# FPGA_Configuration.net
KiCad netlist of a schematic drawn in Altium Designer
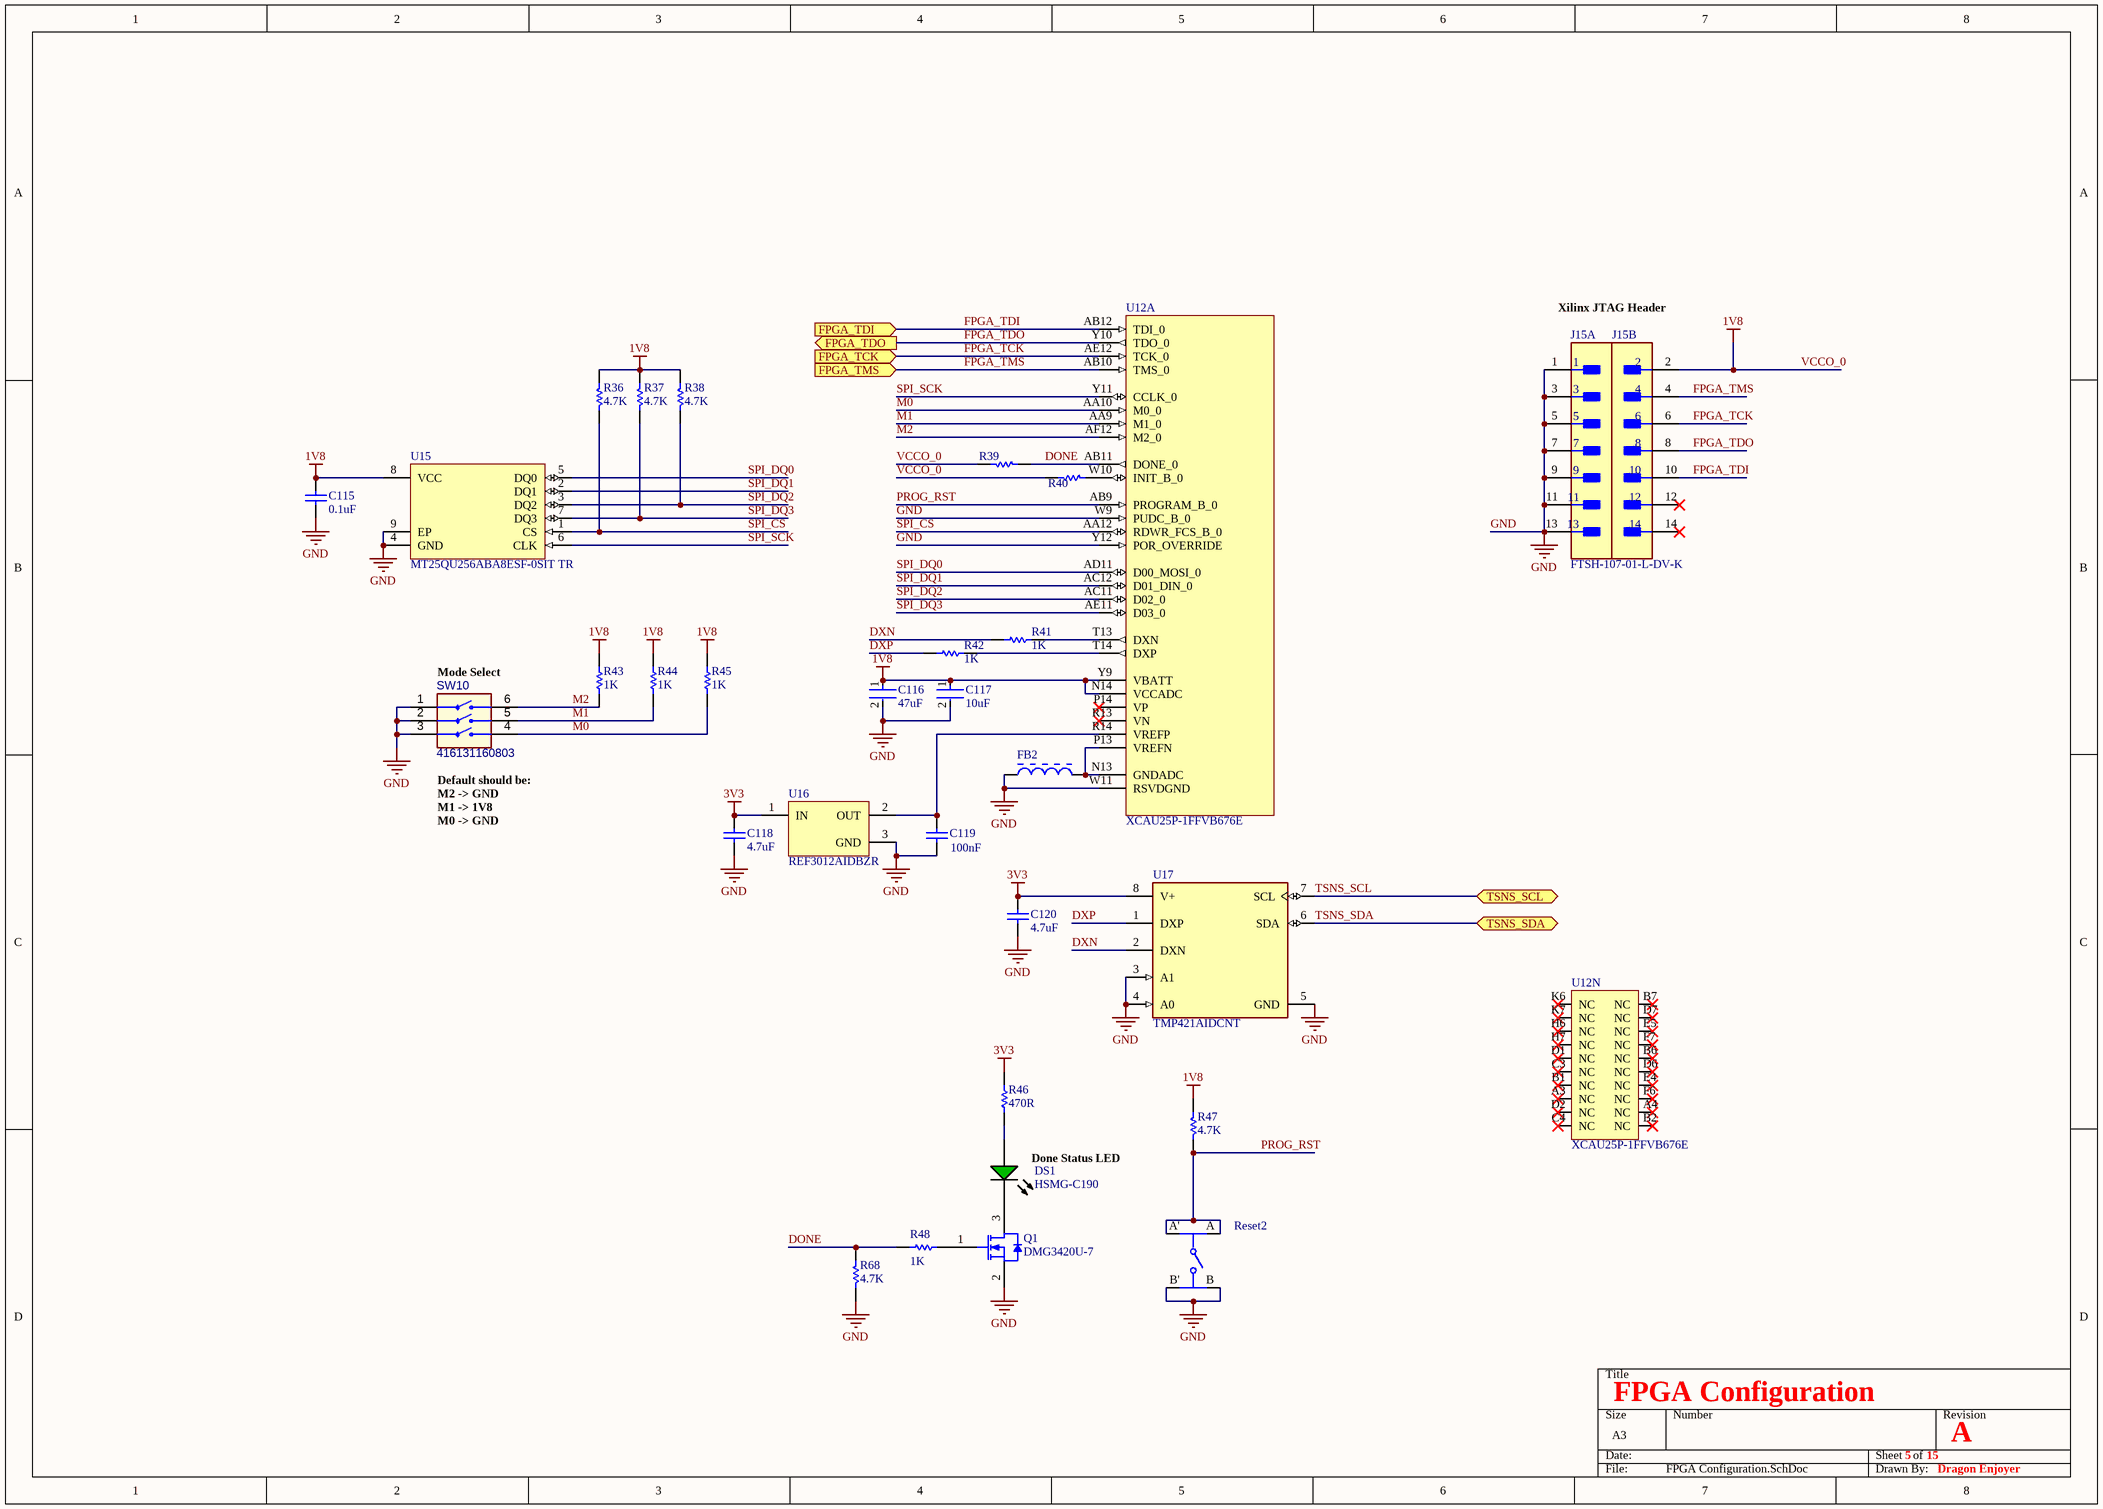
[diagram p0: FPGA Configuration.SchDoc]

(export (version "E")
  (design (tool "Eeschema 10.0.6"))
  (components
    (comp (ref "C115")
      (value "0.1uF")
      (footprint "CAPC1005X56X25LL10T15")
      (fields
        (field (name "MANUFACTURER") "AVX Interconnect / Elco")
        (field (name "PART NUMBER") "04026D104KAT2A")
      )
      (libsource (lib "Altium Content Vault") (part "CAP"))
    )
    (comp (ref "C116")
      (value "GRM188C80E476ME05D")
      (footprint "FP-GRM188-0_2-IPC_C")
      (description "Chip Multilayer Ceramic Capacitors for General Purpose, 0603, 47uF, X6S, 22%, 20%, 2.5V")
      (fields (field (name "TOLERANCE") "20%") (field (name "CAPACITANCE") "47uF"))
      (libsource (lib "Altium Content Vault") (part "11868f565c42a9108669ba33697ecf6"))
    )
    (comp (ref "C117")
      (value "GRM155C80J106ME11D")
      (footprint "FP-GRM15-0_2-MFG")
      (description "CAP CER 10UF 6.3V X6S 0402")
      (fields
        (field (name "TOLERANCE") "20%")
        (field (name "OCTOPART") "https://octopart.com/grm155c80j106me11d-murata-71220993")
        (field (name "CAPACITANCE") "10uF")
      )
      (libsource (lib "Altium Content Vault") (part "b4654b650e69147ec39a6b967a45e02"))
    )
    (comp (ref "C118")
      (value "4.7uF")
      (footprint "CAPC2013X135X45NL10T25")
      (fields (field (name "PART NUMBER") "GRM21BR61E475KA12L") (field (name "MANUFACTURER") "Murata"))
      (libsource (lib "Altium Content Vault") (part "CAP"))
    )
    (comp (ref "C119")
      (value "GRM188R71H104KA93D")
      (footprint "CAPC1608X90X35ML10T15")
      (description "Chip Capacitor, 0.1 uF, +/- 10%, 50 V, -55 to 125 degC, 0603 (1608 Metric), RoHS, Tape and Reel")
      (fields
        (field (name "TOLERANCE") "10%")
        (field (name "CAPACITANCE") "100nF")
        (field (name "VOLTAGE") "50V")
      )
      (libsource (lib "Altium Content Vault") (part "CAP-NP-2"))
    )
    (comp (ref "C120")
      (value "4.7uF")
      (footprint "CAPC2013X135X45NL10T25")
      (fields (field (name "PART NUMBER") "GRM21BR61E475KA12L") (field (name "MANUFACTURER") "Murata"))
      (libsource (lib "Altium Content Vault") (part "CAP"))
    )
    (comp (ref "DS1")
      (value "HSMG-C190")
      (footprint "AVAG-HSMX-C190_V")
      (description "Chip LED, Green, 2.2 V, -40 to 85 degC, 2-Pin SMD, RoHS, Tape and Reel")
      (libsource (lib "Altium Content Vault") (part "LED-GREEN-AK-2"))
    )
    (comp (ref "FB2")
      (value "BLM15AG100SN1D")
      (footprint "MURA-BLM15-CHIP-2_V")
      (fields (field (name "MANUFACTURER") "Murata"))
      (libsource (lib "Altium Content Vault") (part "MURA-FB-2"))
    )
    (comp (ref "J15")
      (value "FTSH-107-01-L-DV-K")
      (footprint "FP-FTSH-107-01-L-DV-K-MFG")
      (description "CONN HEADER SMD 14POS 1.27MM")
      (libsource (lib "") (part "7644e1a88aa4da17242a9b8d8257442_1"))
    )
    (comp (ref "Q1")
      (value "DMG3420U-7")
      (footprint "DIOD-SOT23-3_B_V")
      (description "N-Channel Enhancement Mode MOSFET, 20 V, -55 to 150 degC, 3-Pin SOT23, RoHS, Tape and Reel")
      (fields (field (name "MANUFACTURER") "Diodes Inc"))
      (libsource (lib "Altium Content Vault") (part "NEMOS-GSD-3"))
    )
    (comp (ref "R36")
      (value "4.7K")
      (footprint "RESC1005X40X25LL05T10")
      (fields (field (name "PART NUMBER") "RC0402JR-074K7L") (field (name "MANUFACTURER") "Yageo / Phycomp"))
      (libsource (lib "Altium Content Vault") (part "RES"))
    )
    (comp (ref "R37")
      (value "4.7K")
      (footprint "RESC1005X40X25LL05T10")
      (fields (field (name "PART NUMBER") "RC0402JR-074K7L") (field (name "MANUFACTURER") "Yageo / Phycomp"))
      (libsource (lib "Altium Content Vault") (part "RES"))
    )
    (comp (ref "R38")
      (value "4.7K")
      (footprint "RESC1005X40X25LL05T10")
      (fields (field (name "PART NUMBER") "RC0402JR-074K7L") (field (name "MANUFACTURER") "Yageo / Phycomp"))
      (libsource (lib "Altium Content Vault") (part "RES"))
    )
    (comp (ref "R39")
      (value "RC0402JR-074K7L")
      (footprint "RESC1005X40X25LL05T10")
      (fields (field (name "MANUFACTURER") "Yageo / Phycomp"))
      (libsource (lib "Altium Content Vault") (part "RES"))
    )
    (comp (ref "R40")
      (value "RC0402JR-074K7L")
      (footprint "RESC1005X40X25LL05T10")
      (fields (field (name "MANUFACTURER") "Yageo / Phycomp"))
      (libsource (lib "Altium Content Vault") (part "RES"))
    )
    (comp (ref "R41")
      (value "1K")
      (footprint "RESC1005X40X25NL05T10")
      (fields (field (name "PART NUMBER") "RC0402FR-071KL") (field (name "MANUFACTURER") "Yageo / Phycomp"))
      (libsource (lib "Altium Content Vault") (part "RES"))
    )
    (comp (ref "R42")
      (value "1K")
      (footprint "RESC1005X40X25NL05T10")
      (fields (field (name "PART NUMBER") "RC0402FR-071KL") (field (name "MANUFACTURER") "Yageo / Phycomp"))
      (libsource (lib "Altium Content Vault") (part "RES"))
    )
    (comp (ref "R43")
      (value "1K")
      (footprint "RESC1005X40X25NL05T10")
      (fields (field (name "PART NUMBER") "RC0402FR-071KL") (field (name "MANUFACTURER") "Yageo / Phycomp"))
      (libsource (lib "Altium Content Vault") (part "RES"))
    )
    (comp (ref "R44")
      (value "1K")
      (footprint "RESC1005X40X25NL05T10")
      (fields (field (name "PART NUMBER") "RC0402FR-071KL") (field (name "MANUFACTURER") "Yageo / Phycomp"))
      (libsource (lib "Altium Content Vault") (part "RES"))
    )
    (comp (ref "R45")
      (value "1K")
      (footprint "RESC1005X40X25NL05T10")
      (fields (field (name "PART NUMBER") "RC0402FR-071KL") (field (name "MANUFACTURER") "Yageo / Phycomp"))
      (libsource (lib "Altium Content Vault") (part "RES"))
    )
    (comp (ref "R46")
      (value "470R")
      (footprint "RESC0603X26X15LL03T05")
      (fields (field (name "MANUFACTURER") "Panasonic") (field (name "PART NUMBER") "ERJ1GNF4700C"))
      (libsource (lib "Altium Content Vault") (part "RES"))
    )
    (comp (ref "R47")
      (value "4.7K")
      (footprint "RESC1005X40X25LL05T10")
      (fields (field (name "PART NUMBER") "RC0402JR-074K7L") (field (name "MANUFACTURER") "Yageo / Phycomp"))
      (libsource (lib "Altium Content Vault") (part "RES"))
    )
    (comp (ref "R48")
      (value "1K")
      (footprint "RESC1005X40X25NL05T10")
      (fields (field (name "PART NUMBER") "RC0402FR-071KL") (field (name "MANUFACTURER") "Yageo / Phycomp"))
      (libsource (lib "Altium Content Vault") (part "RES"))
    )
    (comp (ref "R68")
      (value "4.7K")
      (footprint "RESC1005X40X25LL05T10")
      (fields (field (name "PART NUMBER") "RC0402JR-074K7L") (field (name "MANUFACTURER") "Yageo / Phycomp"))
      (libsource (lib "Altium Content Vault") (part "RES"))
    )
    (comp (ref "Reset2")
      (value "EVQ-Q2U03W")
      (footprint "FP-EVQQ2-MFG")
      (description "SWITCH TACTILE SPST-NO 0.02A 15V")
      (fields
        (field (name "MANUFACTURER") "Panasonic")
        (field (name "OCTOPART") "https://octopart.com/evq-q2u03w-panasonic-1404553")
      )
      (libsource (lib "Altium Content Vault") (part "9677229990528492022b31d4503349f"))
    )
    (comp (ref "SW10")
      (value "416131160803")
      (footprint "416131160803")
      (description "WS-DISV 1.27 mm small compact SMD Dip Switch with top tape")
      (libsource (lib "Main Workspace") (part "CMP-00567-2"))
    )
    (comp (ref "U12")
      (value "XCAU25P-1FFVB676E")
      (footprint "BGA676C100P26X26_2600X2600X352")
      (description "FPGA XCAU25 Family 308437 Logic Units 308437 Cells 0.85V 676-Pin FCBGA")
      (libsource (lib "Main Workspace") (part "XCAU25P-1FFVB676E"))
    )
    (comp (ref "U15")
      (value "MT25QU256ABA8ESF-0SIT TR")
      (footprint "SON127P800X75_HS-9N")
      (description "NOR Flash 256Mbit 32M X 8bit Serial-SPI 1.8V 5ns/6ns 16-Pin SOP T/R")
      (libsource (lib "Main Workspace") (part "MT25QU256ABA8ESF-0SIT"))
    )
    (comp (ref "U16")
      (value "REF3012AIDBZR")
      (footprint "DBZ0003A_M")
      (fields (field (name "MANUFACTURER") "Texas Instruments"))
      (libsource (lib "Altium Content Vault") (part "TI-REF3012DBZ3"))
    )
    (comp (ref "U17")
      (value "TMP421AIDCNT")
      (footprint "FP-DCN0008A-IPC_C")
      (description "SENSOR DIGITAL -40C-125C SOT23-8")
      (libsource (lib "Altium Content Vault") (part "ac2e74f630a3703365ce1dfb6254de2"))
    )
  )
  (nets
    (net (code "1") (name "/DONE") (class "Default")
      (node (ref "R39") (pin "1") (pinfunction "1_1") (pintype "passive"))
      (node (ref "R48") (pin "1") (pinfunction "1_1") (pintype "passive"))
      (node (ref "R68") (pin "1") (pinfunction "1_1") (pintype "passive"))
      (node (ref "U12") (pin "AB11") (pinfunction "DONE_0_AB11") (pintype "output"))
    )
    (net (code "2") (name "/DXN") (class "Default")
      (node (ref "R41") (pin "1") (pinfunction "1_1") (pintype "passive"))
      (node (ref "U17") (pin "2") (pinfunction "DXN_2") (pintype "passive"))
    )
    (net (code "3") (name "/DXP") (class "Default")
      (node (ref "R42") (pin "1") (pinfunction "1_1") (pintype "passive"))
      (node (ref "U17") (pin "1") (pinfunction "DXP_1") (pintype "passive"))
    )
    (net (code "4") (name "/FPGA_TCK") (class "Default")
      (node (ref "J15") (pin "6") (pinfunction "6_6") (pintype "passive"))
      (node (ref "U12") (pin "AE12") (pinfunction "TCK_0_AE12") (pintype "input"))
    )
    (net (code "5") (name "/FPGA_TDI") (class "Default")
      (node (ref "J15") (pin "10") (pinfunction "10_10") (pintype "passive"))
      (node (ref "U12") (pin "AB12") (pinfunction "TDI_0_AB12") (pintype "input"))
    )
    (net (code "6") (name "/FPGA_TDO") (class "Default")
      (node (ref "J15") (pin "8") (pinfunction "8_8") (pintype "passive"))
      (node (ref "U12") (pin "Y10") (pinfunction "TDO_0_Y10") (pintype "output"))
    )
    (net (code "7") (name "/FPGA_TMS") (class "Default")
      (node (ref "J15") (pin "4") (pinfunction "4_4") (pintype "passive"))
      (node (ref "U12") (pin "AB10") (pinfunction "TMS_0_AB10") (pintype "input"))
    )
    (net (code "8") (name "/M0") (class "Default")
      (node (ref "R45") (pin "2") (pinfunction "2_2") (pintype "passive"))
      (node (ref "SW10") (pin "4") (pinfunction "4_4") (pintype "passive"))
      (node (ref "U12") (pin "AA10") (pinfunction "M0_0_AA10") (pintype "input"))
    )
    (net (code "9") (name "/M1") (class "Default")
      (node (ref "R44") (pin "1") (pinfunction "1_1") (pintype "passive"))
      (node (ref "SW10") (pin "5") (pinfunction "5_5") (pintype "passive"))
      (node (ref "U12") (pin "AA9") (pinfunction "M1_0_AA9") (pintype "input"))
    )
    (net (code "10") (name "/M2") (class "Default")
      (node (ref "R43") (pin "1") (pinfunction "1_1") (pintype "passive"))
      (node (ref "SW10") (pin "6") (pinfunction "6_6") (pintype "passive"))
      (node (ref "U12") (pin "AF12") (pinfunction "M2_0_AF12") (pintype "input"))
    )
    (net (code "11") (name "/PROG_RST") (class "Default")
      (node (ref "R47") (pin "2") (pinfunction "2_2") (pintype "passive"))
      (node (ref "Reset2") (pin "A") (pinfunction "A_A") (pintype "passive"))
      (node (ref "Reset2") (pin "A'") (pinfunction "A'_A'") (pintype "passive"))
      (node (ref "U12") (pin "AB9") (pinfunction "PROGRAM_B_0_AB9") (pintype "input"))
    )
    (net (code "12") (name "/SPI_CS") (class "Default")
      (node (ref "R36") (pin "2") (pinfunction "2_2") (pintype "passive"))
      (node (ref "U12") (pin "AA12") (pinfunction "RDWR_FCS_B_0_AA12") (pintype "bidirectional"))
      (node (ref "U15") (pin "1") (pinfunction "CS_1") (pintype "input"))
    )
    (net (code "13") (name "/SPI_DQ0") (class "Default")
      (node (ref "U12") (pin "AD11") (pinfunction "D00_MOSI_0_AD11") (pintype "bidirectional"))
      (node (ref "U15") (pin "5") (pinfunction "DQ0_5") (pintype "bidirectional"))
    )
    (net (code "14") (name "/SPI_DQ1") (class "Default")
      (node (ref "U12") (pin "AC12") (pinfunction "D01_DIN_0_AC12") (pintype "bidirectional"))
      (node (ref "U15") (pin "2") (pinfunction "DQ1_2") (pintype "bidirectional"))
    )
    (net (code "15") (name "/SPI_DQ2") (class "Default")
      (node (ref "R38") (pin "2") (pinfunction "2_2") (pintype "passive"))
      (node (ref "U12") (pin "AC11") (pinfunction "D02_0_AC11") (pintype "bidirectional"))
      (node (ref "U15") (pin "3") (pinfunction "DQ2_3") (pintype "bidirectional"))
    )
    (net (code "16") (name "/SPI_DQ3") (class "Default")
      (node (ref "R37") (pin "2") (pinfunction "2_2") (pintype "passive"))
      (node (ref "U12") (pin "AE11") (pinfunction "D03_0_AE11") (pintype "bidirectional"))
      (node (ref "U15") (pin "7") (pinfunction "DQ3_7") (pintype "bidirectional"))
    )
    (net (code "17") (name "/SPI_SCK") (class "Default")
      (node (ref "U12") (pin "Y11") (pinfunction "CCLK_0_Y11") (pintype "bidirectional"))
      (node (ref "U15") (pin "6") (pinfunction "CLK_6") (pintype "input"))
    )
    (net (code "18") (name "/TSNS_SCL") (class "Default")
      (node (ref "U17") (pin "7") (pinfunction "SCL_7") (pintype "bidirectional"))
    )
    (net (code "19") (name "/TSNS_SDA") (class "Default")
      (node (ref "U17") (pin "6") (pinfunction "SDA_6") (pintype "bidirectional"))
    )
    (net (code "20") (name "1V8") (class "Default")
      (node (ref "C115") (pin "2") (pinfunction "2_2") (pintype "passive"))
      (node (ref "C116") (pin "1") (pinfunction "1_1") (pintype "passive"))
      (node (ref "C117") (pin "1") (pinfunction "1_1") (pintype "passive"))
      (node (ref "J15") (pin "2") (pinfunction "2_2") (pintype "passive"))
      (node (ref "R36") (pin "1") (pinfunction "1_1") (pintype "passive"))
      (node (ref "R37") (pin "1") (pinfunction "1_1") (pintype "passive"))
      (node (ref "R38") (pin "1") (pinfunction "1_1") (pintype "passive"))
      (node (ref "R39") (pin "2") (pinfunction "2_2") (pintype "passive"))
      (node (ref "R40") (pin "2") (pinfunction "2_2") (pintype "passive"))
      (node (ref "R43") (pin "2") (pinfunction "2_2") (pintype "passive"))
      (node (ref "R44") (pin "2") (pinfunction "2_2") (pintype "passive"))
      (node (ref "R45") (pin "1") (pinfunction "1_1") (pintype "passive"))
      (node (ref "R47") (pin "1") (pinfunction "1_1") (pintype "passive"))
      (node (ref "U12") (pin "N14") (pinfunction "VCCADC_N14") (pintype "passive"))
      (node (ref "U12") (pin "Y9") (pinfunction "VBATT_Y9") (pintype "passive"))
      (node (ref "U15") (pin "8") (pinfunction "VCC_8") (pintype "passive"))
    )
    (net (code "21") (name "3V3") (class "Default")
      (node (ref "C118") (pin "1") (pinfunction "1_1") (pintype "passive"))
      (node (ref "C120") (pin "1") (pinfunction "1_1") (pintype "passive"))
      (node (ref "R46") (pin "1") (pinfunction "1_1") (pintype "passive"))
      (node (ref "U16") (pin "1") (pinfunction "IN_1") (pintype "power_in"))
      (node (ref "U17") (pin "8") (pinfunction "V+_8") (pintype "power_in"))
    )
    (net (code "22") (name "GND") (class "Default")
      (node (ref "C115") (pin "1") (pinfunction "1_1") (pintype "passive"))
      (node (ref "C116") (pin "2") (pinfunction "2_2") (pintype "passive"))
      (node (ref "C117") (pin "2") (pinfunction "2_2") (pintype "passive"))
      (node (ref "C118") (pin "2") (pinfunction "2_2") (pintype "passive"))
      (node (ref "C119") (pin "1") (pinfunction "1_1") (pintype "passive"))
      (node (ref "C120") (pin "2") (pinfunction "2_2") (pintype "passive"))
      (node (ref "FB2") (pin "1") (pinfunction "1_1") (pintype "passive"))
      (node (ref "J15") (pin "1") (pinfunction "1_1") (pintype "passive"))
      (node (ref "J15") (pin "11") (pinfunction "11_11") (pintype "passive"))
      (node (ref "J15") (pin "13") (pinfunction "13_13") (pintype "passive"))
      (node (ref "J15") (pin "3") (pinfunction "3_3") (pintype "passive"))
      (node (ref "J15") (pin "5") (pinfunction "5_5") (pintype "passive"))
      (node (ref "J15") (pin "7") (pinfunction "7_7") (pintype "passive"))
      (node (ref "J15") (pin "9") (pinfunction "9_9") (pintype "passive"))
      (node (ref "Q1") (pin "2") (pinfunction "S_2") (pintype "passive"))
      (node (ref "R68") (pin "2") (pinfunction "2_2") (pintype "passive"))
      (node (ref "Reset2") (pin "B") (pinfunction "B_B") (pintype "passive"))
      (node (ref "Reset2") (pin "B'") (pinfunction "B'_B'") (pintype "passive"))
      (node (ref "SW10") (pin "1") (pinfunction "1_1") (pintype "passive"))
      (node (ref "SW10") (pin "2") (pinfunction "2_2") (pintype "passive"))
      (node (ref "SW10") (pin "3") (pinfunction "3_3") (pintype "passive"))
      (node (ref "U12") (pin "W11") (pinfunction "RSVDGND_W11") (pintype "passive"))
      (node (ref "U12") (pin "W9") (pinfunction "PUDC_B_0_W9") (pintype "input"))
      (node (ref "U12") (pin "Y12") (pinfunction "POR_OVERRIDE_Y12") (pintype "input"))
      (node (ref "U15") (pin "4") (pinfunction "GND_4") (pintype "passive"))
      (node (ref "U15") (pin "9") (pinfunction "EP_9") (pintype "passive"))
      (node (ref "U16") (pin "3") (pinfunction "GND_3") (pintype "passive"))
      (node (ref "U17") (pin "3") (pinfunction "A1_3") (pintype "input"))
      (node (ref "U17") (pin "4") (pinfunction "A0_4") (pintype "input"))
      (node (ref "U17") (pin "5") (pinfunction "GND_5") (pintype "passive"))
    )
    (net (code "23") (name "Net-(DS1-A)") (class "Default")
      (node (ref "DS1") (pin "1") (pinfunction "A_1") (pintype "passive"))
      (node (ref "R46") (pin "2") (pinfunction "2_2") (pintype "passive"))
    )
    (net (code "24") (name "Net-(DS1-K)") (class "Default")
      (node (ref "DS1") (pin "2") (pinfunction "K_2") (pintype "passive"))
      (node (ref "Q1") (pin "3") (pinfunction "D_3") (pintype "passive"))
    )
    (net (code "25") (name "Net-(Q1-G)") (class "Default")
      (node (ref "Q1") (pin "1") (pinfunction "G_1") (pintype "passive"))
      (node (ref "R48") (pin "2") (pinfunction "2_2") (pintype "passive"))
    )
    (net (code "26") (name "Net-(U12A-DXN)") (class "Default")
      (node (ref "R41") (pin "2") (pinfunction "2_2") (pintype "passive"))
      (node (ref "U12") (pin "T13") (pinfunction "DXN_T13") (pintype "output"))
    )
    (net (code "27") (name "Net-(U12A-DXP)") (class "Default")
      (node (ref "R42") (pin "2") (pinfunction "2_2") (pintype "passive"))
      (node (ref "U12") (pin "T14") (pinfunction "DXP_T14") (pintype "output"))
    )
    (net (code "28") (name "Net-(U12A-GNDADC)") (class "Default")
      (node (ref "FB2") (pin "2") (pinfunction "2_2") (pintype "passive"))
      (node (ref "U12") (pin "N13") (pinfunction "GNDADC_N13") (pintype "passive"))
      (node (ref "U12") (pin "P13") (pinfunction "VREFN_P13") (pintype "passive"))
    )
    (net (code "29") (name "Net-(U12A-INIT_B_0)") (class "Default")
      (node (ref "R40") (pin "1") (pinfunction "1_1") (pintype "passive"))
      (node (ref "U12") (pin "W10") (pinfunction "INIT_B_0_W10") (pintype "bidirectional"))
    )
    (net (code "30") (name "Net-(U12A-VREFP)") (class "Default")
      (node (ref "C119") (pin "2") (pinfunction "2_2") (pintype "passive"))
      (node (ref "U12") (pin "R14") (pinfunction "VREFP_R14") (pintype "passive"))
      (node (ref "U16") (pin "2") (pinfunction "OUT_2") (pintype "power_in"))
    )
    (net (code "31") (name "unconnected-(J15-Pad12)") (class "Default")
      (node (ref "J15") (pin "12") (pinfunction "12_12") (pintype "passive+no_connect"))
    )
    (net (code "32") (name "unconnected-(J15-Pad14)") (class "Default")
      (node (ref "J15") (pin "14") (pinfunction "14_14") (pintype "passive+no_connect"))
    )
    (net (code "33") (name "unconnected-(U12A-VN-PadR13)") (class "Default")
      (node (ref "U12") (pin "R13") (pinfunction "VN_R13") (pintype "passive+no_connect"))
    )
    (net (code "34") (name "unconnected-(U12A-VP-PadP14)") (class "Default")
      (node (ref "U12") (pin "P14") (pinfunction "VP_P14") (pintype "passive+no_connect"))
    )
    (net (code "35") (name "unconnected-(U12N-NC-PadA3)") (class "Default")
      (node (ref "U12") (pin "A3") (pinfunction "NC_A3") (pintype "passive+no_connect"))
    )
    (net (code "36") (name "unconnected-(U12N-NC-PadA4)") (class "Default")
      (node (ref "U12") (pin "A4") (pinfunction "NC_A4") (pintype "passive+no_connect"))
    )
    (net (code "37") (name "unconnected-(U12N-NC-PadB1)") (class "Default")
      (node (ref "U12") (pin "B1") (pinfunction "NC_B1") (pintype "passive+no_connect"))
    )
    (net (code "38") (name "unconnected-(U12N-NC-PadB2)") (class "Default")
      (node (ref "U12") (pin "B2") (pinfunction "NC_B2") (pintype "passive+no_connect"))
    )
    (net (code "39") (name "unconnected-(U12N-NC-PadB6)") (class "Default")
      (node (ref "U12") (pin "B6") (pinfunction "NC_B6") (pintype "passive+no_connect"))
    )
    (net (code "40") (name "unconnected-(U12N-NC-PadB7)") (class "Default")
      (node (ref "U12") (pin "B7") (pinfunction "NC_B7") (pintype "passive+no_connect"))
    )
    (net (code "41") (name "unconnected-(U12N-NC-PadC3)") (class "Default")
      (node (ref "U12") (pin "C3") (pinfunction "NC_C3") (pintype "passive+no_connect"))
    )
    (net (code "42") (name "unconnected-(U12N-NC-PadC4)") (class "Default")
      (node (ref "U12") (pin "C4") (pinfunction "NC_C4") (pintype "passive+no_connect"))
    )
    (net (code "43") (name "unconnected-(U12N-NC-PadD1)") (class "Default")
      (node (ref "U12") (pin "D1") (pinfunction "NC_D1") (pintype "passive+no_connect"))
    )
    (net (code "44") (name "unconnected-(U12N-NC-PadD2)") (class "Default")
      (node (ref "U12") (pin "D2") (pinfunction "NC_D2") (pintype "passive+no_connect"))
    )
    (net (code "45") (name "unconnected-(U12N-NC-PadD6)") (class "Default")
      (node (ref "U12") (pin "D6") (pinfunction "NC_D6") (pintype "passive+no_connect"))
    )
    (net (code "46") (name "unconnected-(U12N-NC-PadD7)") (class "Default")
      (node (ref "U12") (pin "D7") (pinfunction "NC_D7") (pintype "passive+no_connect"))
    )
    (net (code "47") (name "unconnected-(U12N-NC-PadE4)") (class "Default")
      (node (ref "U12") (pin "E4") (pinfunction "NC_E4") (pintype "passive+no_connect"))
    )
    (net (code "48") (name "unconnected-(U12N-NC-PadE5)") (class "Default")
      (node (ref "U12") (pin "E5") (pinfunction "NC_E5") (pintype "passive+no_connect"))
    )
    (net (code "49") (name "unconnected-(U12N-NC-PadF6)") (class "Default")
      (node (ref "U12") (pin "F6") (pinfunction "NC_F6") (pintype "passive+no_connect"))
    )
    (net (code "50") (name "unconnected-(U12N-NC-PadF7)") (class "Default")
      (node (ref "U12") (pin "F7") (pinfunction "NC_F7") (pintype "passive+no_connect"))
    )
    (net (code "51") (name "unconnected-(U12N-NC-PadH6)") (class "Default")
      (node (ref "U12") (pin "H6") (pinfunction "NC_H6") (pintype "passive+no_connect"))
    )
    (net (code "52") (name "unconnected-(U12N-NC-PadH7)") (class "Default")
      (node (ref "U12") (pin "H7") (pinfunction "NC_H7") (pintype "passive+no_connect"))
    )
    (net (code "53") (name "unconnected-(U12N-NC-PadK6)") (class "Default")
      (node (ref "U12") (pin "K6") (pinfunction "NC_K6") (pintype "passive+no_connect"))
    )
    (net (code "54") (name "unconnected-(U12N-NC-PadK7)") (class "Default")
      (node (ref "U12") (pin "K7") (pinfunction "NC_K7") (pintype "passive+no_connect"))
    )
  )
)
